# reflowserial.net
KiCad netlist of a schematic drawn in EAGLE
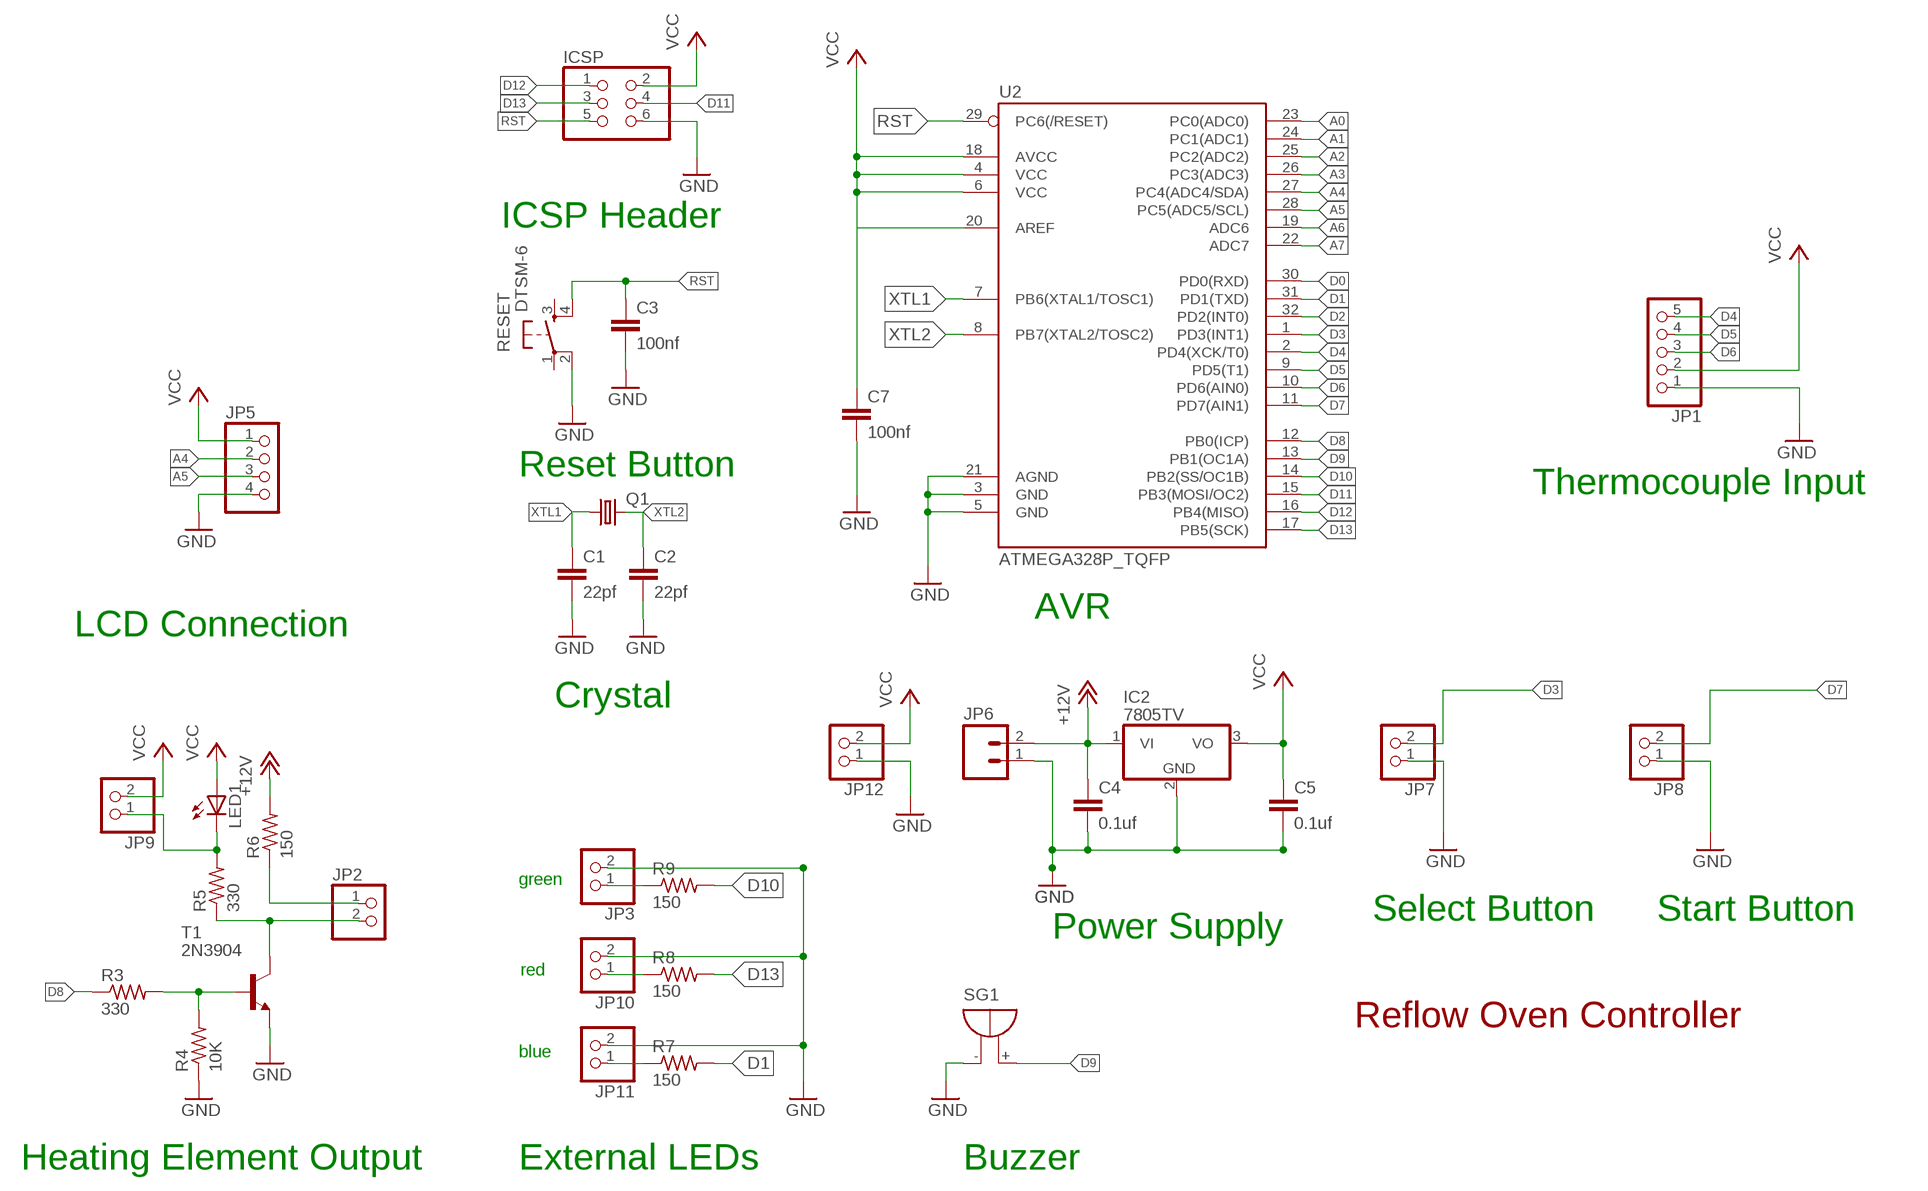
[diagram p0: schematic, sheet 1]

(export (version "E")
  (design (tool "Eeschema 10.0.6"))
  (components
    (comp (ref "C1")
      (value "22pf")
      (footprint "eagle-import:C0805")
      (libsource (lib "eagle-import") (part "C-EUC0805"))
    )
    (comp (ref "C2")
      (value "22pf")
      (footprint "eagle-import:C0805")
      (libsource (lib "eagle-import") (part "C-EUC0805"))
    )
    (comp (ref "C3")
      (value "100nf")
      (footprint "eagle-import:C0805")
      (libsource (lib "eagle-import") (part "C-EUC0805"))
    )
    (comp (ref "C4")
      (value "0.1uf")
      (footprint "eagle-import:C0805")
      (libsource (lib "eagle-import") (part "C-EUC0805"))
    )
    (comp (ref "C5")
      (value "0.1uf")
      (footprint "eagle-import:C0805")
      (libsource (lib "eagle-import") (part "C-EUC0805"))
    )
    (comp (ref "C7")
      (value "100nf")
      (footprint "eagle-import:C0805")
      (libsource (lib "eagle-import") (part "C-EUC0805"))
    )
    (comp (ref "IC2")
      (value "7805TV")
      (footprint "eagle-import:TO220V")
      (libsource (lib "eagle-import") (part "78TV05"))
    )
    (comp (ref "ICSP")
      (value "PINHD-2X3")
      (footprint "eagle-import:2X03")
      (libsource (lib "eagle-import") (part "PINHD-2X3"))
    )
    (comp (ref "JP1")
      (value "PINHD-1X5")
      (footprint "eagle-import:1X05")
      (libsource (lib "eagle-import") (part "PINHD-1X5"))
    )
    (comp (ref "JP2")
      (value "PINHD-1X2")
      (footprint "eagle-import:1X02")
      (libsource (lib "eagle-import") (part "PINHD-1X2"))
    )
    (comp (ref "JP3")
      (value "PINHD-1X2")
      (footprint "eagle-import:1X02")
      (libsource (lib "eagle-import") (part "PINHD-1X2"))
    )
    (comp (ref "JP5")
      (value "PINHD-1X4")
      (footprint "eagle-import:1X04")
      (libsource (lib "eagle-import") (part "PINHD-1X4"))
    )
    (comp (ref "JP6")
      (value "M023.5MM")
      (footprint "eagle-import:SCREWTERMINAL-3.5MM-2")
      (libsource (lib "eagle-import") (part "M023.5MM"))
    )
    (comp (ref "JP7")
      (value "PINHD-1X2")
      (footprint "eagle-import:1X02")
      (libsource (lib "eagle-import") (part "PINHD-1X2"))
    )
    (comp (ref "JP8")
      (value "PINHD-1X2")
      (footprint "eagle-import:1X02")
      (libsource (lib "eagle-import") (part "PINHD-1X2"))
    )
    (comp (ref "JP9")
      (value "PINHD-1X2")
      (footprint "eagle-import:1X02")
      (libsource (lib "eagle-import") (part "PINHD-1X2"))
    )
    (comp (ref "JP10")
      (value "PINHD-1X2")
      (footprint "eagle-import:1X02")
      (libsource (lib "eagle-import") (part "PINHD-1X2"))
    )
    (comp (ref "JP11")
      (value "PINHD-1X2")
      (footprint "eagle-import:1X02")
      (libsource (lib "eagle-import") (part "PINHD-1X2"))
    )
    (comp (ref "JP12")
      (value "PINHD-1X2")
      (footprint "eagle-import:1X02")
      (libsource (lib "eagle-import") (part "PINHD-1X2"))
    )
    (comp (ref "LED1")
      (value "LEDSMT1206")
      (footprint "eagle-import:1206")
      (libsource (lib "eagle-import") (part "LEDSMT1206"))
    )
    (comp (ref "Q1")
      (value "CRYSTALSM49")
      (footprint "eagle-import:SM49")
      (libsource (lib "eagle-import") (part "CRYSTALSM49"))
    )
    (comp (ref "R3")
      (value "330")
      (footprint "eagle-import:R0805")
      (libsource (lib "eagle-import") (part "R-US_R0805"))
    )
    (comp (ref "R4")
      (value "10K")
      (footprint "eagle-import:R0805")
      (libsource (lib "eagle-import") (part "R-US_R0805"))
    )
    (comp (ref "R5")
      (value "330")
      (footprint "eagle-import:R0805")
      (libsource (lib "eagle-import") (part "R-US_R0805"))
    )
    (comp (ref "R6")
      (value "150")
      (footprint "eagle-import:R0805")
      (libsource (lib "eagle-import") (part "R-US_R0805"))
    )
    (comp (ref "R7")
      (value "150")
      (footprint "eagle-import:R0805")
      (libsource (lib "eagle-import") (part "R-US_R0805"))
    )
    (comp (ref "R8")
      (value "150")
      (footprint "eagle-import:R0805")
      (libsource (lib "eagle-import") (part "R-US_R0805"))
    )
    (comp (ref "R9")
      (value "150")
      (footprint "eagle-import:R0805")
      (libsource (lib "eagle-import") (part "R-US_R0805"))
    )
    (comp (ref "RESET")
      (value "DTSM-6")
      (footprint "eagle-import:DTSM-6")
      (libsource (lib "eagle-import") (part "DTSM-6"))
    )
    (comp (ref "SG1")
      (value "F/QMBIII")
      (footprint "eagle-import:F_QMBIII")
      (libsource (lib "eagle-import") (part "F/QMBIII"))
    )
    (comp (ref "T1")
      (value "2N3904")
      (footprint "eagle-import:TO92@1")
      (libsource (lib "eagle-import") (part "2N3904"))
    )
    (comp (ref "U2")
      (value "ATMEGA328P_TQFP")
      (footprint "eagle-import:TQFP32-08")
      (libsource (lib "eagle-import") (part "ATMEGA328P_TQFP"))
    )
  )
  (nets
    (net (code "1") (name "+12V") (class "Default")
      (node (ref "C4") (pin "1") (pinfunction "1_1") (pintype "passive"))
      (node (ref "IC2") (pin "1") (pinfunction "VI_1") (pintype "input"))
      (node (ref "JP6") (pin "2") (pinfunction "2_2") (pintype "passive"))
      (node (ref "R6") (pin "2") (pinfunction "2_2") (pintype "passive"))
    )
    (net (code "2") (name "A0") (class "Default")
      (node (ref "U2") (pin "23") (pinfunction "PC0(ADC0)_23") (pintype "bidirectional"))
    )
    (net (code "3") (name "A1") (class "Default")
      (node (ref "U2") (pin "24") (pinfunction "PC1(ADC1)_24") (pintype "bidirectional"))
    )
    (net (code "4") (name "A2") (class "Default")
      (node (ref "U2") (pin "25") (pinfunction "PC2(ADC2)_25") (pintype "bidirectional"))
    )
    (net (code "5") (name "A3") (class "Default")
      (node (ref "U2") (pin "26") (pinfunction "PC3(ADC3)_26") (pintype "bidirectional"))
    )
    (net (code "6") (name "A4") (class "Default")
      (node (ref "JP5") (pin "2") (pinfunction "2_2") (pintype "passive"))
      (node (ref "U2") (pin "27") (pinfunction "PC4(ADC4/SDA)_27") (pintype "bidirectional"))
    )
    (net (code "7") (name "A5") (class "Default")
      (node (ref "JP5") (pin "3") (pinfunction "3_3") (pintype "passive"))
      (node (ref "U2") (pin "28") (pinfunction "PC5(ADC5/SCL)_28") (pintype "bidirectional"))
    )
    (net (code "8") (name "A6") (class "Default")
      (node (ref "U2") (pin "19") (pinfunction "ADC6_19") (pintype "bidirectional"))
    )
    (net (code "9") (name "A7") (class "Default")
      (node (ref "U2") (pin "22") (pinfunction "ADC7_22") (pintype "bidirectional"))
    )
    (net (code "10") (name "D0") (class "Default")
      (node (ref "U2") (pin "30") (pinfunction "PD0(RXD)_30") (pintype "bidirectional"))
    )
    (net (code "11") (name "D1") (class "Default")
      (node (ref "R7") (pin "2") (pinfunction "2_2") (pintype "passive"))
      (node (ref "U2") (pin "31") (pinfunction "PD1(TXD)_31") (pintype "bidirectional"))
    )
    (net (code "12") (name "D2") (class "Default")
      (node (ref "U2") (pin "32") (pinfunction "PD2(INT0)_32") (pintype "bidirectional"))
    )
    (net (code "13") (name "D3") (class "Default")
      (node (ref "JP7") (pin "2") (pinfunction "2_2") (pintype "passive"))
      (node (ref "U2") (pin "1") (pinfunction "PD3(INT1)_1") (pintype "bidirectional"))
    )
    (net (code "14") (name "D4") (class "Default")
      (node (ref "JP1") (pin "5") (pinfunction "5_5") (pintype "passive"))
      (node (ref "U2") (pin "2") (pinfunction "PD4(XCK/T0)_2") (pintype "bidirectional"))
    )
    (net (code "15") (name "D5") (class "Default")
      (node (ref "JP1") (pin "4") (pinfunction "4_4") (pintype "passive"))
      (node (ref "U2") (pin "9") (pinfunction "PD5(T1)_9") (pintype "bidirectional"))
    )
    (net (code "16") (name "D6") (class "Default")
      (node (ref "JP1") (pin "3") (pinfunction "3_3") (pintype "passive"))
      (node (ref "U2") (pin "10") (pinfunction "PD6(AIN0)_10") (pintype "bidirectional"))
    )
    (net (code "17") (name "D7") (class "Default")
      (node (ref "JP8") (pin "2") (pinfunction "2_2") (pintype "passive"))
      (node (ref "U2") (pin "11") (pinfunction "PD7(AIN1)_11") (pintype "bidirectional"))
    )
    (net (code "18") (name "D8") (class "Default")
      (node (ref "R3") (pin "1") (pinfunction "1_1") (pintype "passive"))
      (node (ref "U2") (pin "12") (pinfunction "PB0(ICP)_12") (pintype "bidirectional"))
    )
    (net (code "19") (name "D9") (class "Default")
      (node (ref "SG1") (pin "+") (pinfunction "-_+") (pintype "passive"))
      (node (ref "U2") (pin "13") (pinfunction "PB1(OC1A)_13") (pintype "bidirectional"))
    )
    (net (code "20") (name "D10") (class "Default")
      (node (ref "R9") (pin "2") (pinfunction "2_2") (pintype "passive"))
      (node (ref "U2") (pin "14") (pinfunction "PB2(SS/OC1B)_14") (pintype "bidirectional"))
    )
    (net (code "21") (name "D11") (class "Default")
      (node (ref "ICSP") (pin "4") (pinfunction "4_4") (pintype "passive"))
      (node (ref "U2") (pin "15") (pinfunction "PB3(MOSI/OC2)_15") (pintype "bidirectional"))
    )
    (net (code "22") (name "D12") (class "Default")
      (node (ref "ICSP") (pin "1") (pinfunction "1_1") (pintype "passive"))
      (node (ref "U2") (pin "16") (pinfunction "PB4(MISO)_16") (pintype "bidirectional"))
    )
    (net (code "23") (name "D13") (class "Default")
      (node (ref "ICSP") (pin "3") (pinfunction "3_3") (pintype "passive"))
      (node (ref "R8") (pin "2") (pinfunction "2_2") (pintype "passive"))
      (node (ref "U2") (pin "17") (pinfunction "PB5(SCK)_17") (pintype "bidirectional"))
    )
    (net (code "24") (name "GND") (class "Default")
      (node (ref "C1") (pin "2") (pinfunction "2_2") (pintype "passive"))
      (node (ref "C2") (pin "2") (pinfunction "2_2") (pintype "passive"))
      (node (ref "C3") (pin "2") (pinfunction "2_2") (pintype "passive"))
      (node (ref "C4") (pin "2") (pinfunction "2_2") (pintype "passive"))
      (node (ref "C5") (pin "2") (pinfunction "2_2") (pintype "passive"))
      (node (ref "C7") (pin "2") (pinfunction "2_2") (pintype "passive"))
      (node (ref "IC2") (pin "2") (pinfunction "GND_2") (pintype "passive"))
      (node (ref "ICSP") (pin "6") (pinfunction "6_6") (pintype "passive"))
      (node (ref "JP1") (pin "1") (pinfunction "1_1") (pintype "passive"))
      (node (ref "JP10") (pin "2") (pinfunction "2_2") (pintype "passive"))
      (node (ref "JP11") (pin "2") (pinfunction "2_2") (pintype "passive"))
      (node (ref "JP12") (pin "1") (pinfunction "1_1") (pintype "passive"))
      (node (ref "JP3") (pin "2") (pinfunction "2_2") (pintype "passive"))
      (node (ref "JP5") (pin "4") (pinfunction "4_4") (pintype "passive"))
      (node (ref "JP6") (pin "1") (pinfunction "1_1") (pintype "passive"))
      (node (ref "JP7") (pin "1") (pinfunction "1_1") (pintype "passive"))
      (node (ref "JP8") (pin "1") (pinfunction "1_1") (pintype "passive"))
      (node (ref "R4") (pin "1") (pinfunction "1_1") (pintype "passive"))
      (node (ref "RESET") (pin "2") (pinfunction "2_2") (pintype "passive"))
      (node (ref "SG1") (pin "-") (pinfunction "+_-") (pintype "passive"))
      (node (ref "T1") (pin "3") (pinfunction "E_3") (pintype "passive"))
      (node (ref "U2") (pin "21") (pinfunction "AGND_21") (pintype "bidirectional"))
      (node (ref "U2") (pin "3") (pinfunction "GND_3") (pintype "bidirectional"))
      (node (ref "U2") (pin "5") (pinfunction "GND_5") (pintype "bidirectional"))
    )
    (net (code "25") (name "Net-(JP2-Pad1)") (class "Default")
      (node (ref "JP2") (pin "1") (pinfunction "1_1") (pintype "passive"))
      (node (ref "R6") (pin "1") (pinfunction "1_1") (pintype "passive"))
    )
    (net (code "26") (name "Net-(JP3-Pad1)") (class "Default")
      (node (ref "JP3") (pin "1") (pinfunction "1_1") (pintype "passive"))
      (node (ref "R9") (pin "1") (pinfunction "1_1") (pintype "passive"))
    )
    (net (code "27") (name "Net-(JP9-Pad1)") (class "Default")
      (node (ref "JP9") (pin "1") (pinfunction "1_1") (pintype "passive"))
      (node (ref "LED1") (pin "C") (pinfunction "C_C") (pintype "passive"))
      (node (ref "R5") (pin "2") (pinfunction "2_2") (pintype "passive"))
    )
    (net (code "28") (name "Net-(JP10-Pad1)") (class "Default")
      (node (ref "JP10") (pin "1") (pinfunction "1_1") (pintype "passive"))
      (node (ref "R8") (pin "1") (pinfunction "1_1") (pintype "passive"))
    )
    (net (code "29") (name "Net-(JP11-Pad1)") (class "Default")
      (node (ref "JP11") (pin "1") (pinfunction "1_1") (pintype "passive"))
      (node (ref "R7") (pin "1") (pinfunction "1_1") (pintype "passive"))
    )
    (net (code "30") (name "Net-(T1-B)") (class "Default")
      (node (ref "R3") (pin "2") (pinfunction "2_2") (pintype "passive"))
      (node (ref "R4") (pin "2") (pinfunction "2_2") (pintype "passive"))
      (node (ref "T1") (pin "2") (pinfunction "B_2") (pintype "passive"))
    )
    (net (code "31") (name "Net-(T1-C)") (class "Default")
      (node (ref "JP2") (pin "2") (pinfunction "2_2") (pintype "passive"))
      (node (ref "R5") (pin "1") (pinfunction "1_1") (pintype "passive"))
      (node (ref "T1") (pin "1") (pinfunction "C_1") (pintype "passive"))
    )
    (net (code "32") (name "RST") (class "Default")
      (node (ref "C3") (pin "1") (pinfunction "1_1") (pintype "passive"))
      (node (ref "ICSP") (pin "5") (pinfunction "5_5") (pintype "passive"))
      (node (ref "RESET") (pin "4") (pinfunction "4_4") (pintype "passive"))
      (node (ref "U2") (pin "29") (pinfunction "PC6(/RESET)_29") (pintype "bidirectional"))
    )
    (net (code "33") (name "VCC") (class "Default")
      (node (ref "C5") (pin "1") (pinfunction "1_1") (pintype "passive"))
      (node (ref "C7") (pin "1") (pinfunction "1_1") (pintype "passive"))
      (node (ref "IC2") (pin "3") (pinfunction "VO_3") (pintype "passive"))
      (node (ref "ICSP") (pin "2") (pinfunction "2_2") (pintype "passive"))
      (node (ref "JP1") (pin "2") (pinfunction "2_2") (pintype "passive"))
      (node (ref "JP12") (pin "2") (pinfunction "2_2") (pintype "passive"))
      (node (ref "JP5") (pin "1") (pinfunction "1_1") (pintype "passive"))
      (node (ref "JP9") (pin "2") (pinfunction "2_2") (pintype "passive"))
      (node (ref "LED1") (pin "A") (pinfunction "A_A") (pintype "passive"))
      (node (ref "U2") (pin "18") (pinfunction "AVCC_18") (pintype "bidirectional"))
      (node (ref "U2") (pin "20") (pinfunction "AREF_20") (pintype "bidirectional"))
      (node (ref "U2") (pin "4") (pinfunction "VCC_4") (pintype "bidirectional"))
      (node (ref "U2") (pin "6") (pinfunction "VCC_6") (pintype "bidirectional"))
    )
    (net (code "34") (name "XTL1") (class "Default")
      (node (ref "C1") (pin "1") (pinfunction "1_1") (pintype "passive"))
      (node (ref "Q1") (pin "1") (pinfunction "1_1") (pintype "passive"))
      (node (ref "U2") (pin "7") (pinfunction "PB6(XTAL1/TOSC1)_7") (pintype "bidirectional"))
    )
    (net (code "35") (name "XTL2") (class "Default")
      (node (ref "C2") (pin "1") (pinfunction "1_1") (pintype "passive"))
      (node (ref "Q1") (pin "2") (pinfunction "2_2") (pintype "passive"))
      (node (ref "U2") (pin "8") (pinfunction "PB7(XTAL2/TOSC2)_8") (pintype "bidirectional"))
    )
    (net (code "36") (name "unconnected-(RESET-Pad1)") (class "Default")
      (node (ref "RESET") (pin "1") (pinfunction "1_1") (pintype "passive"))
    )
    (net (code "37") (name "unconnected-(RESET-Pad3)") (class "Default")
      (node (ref "RESET") (pin "3") (pinfunction "3_3") (pintype "passive"))
    )
  )
)
